# SCH_New_Project_2024-01-06.net
KiCad netlist of a schematic drawn in EasyEDA
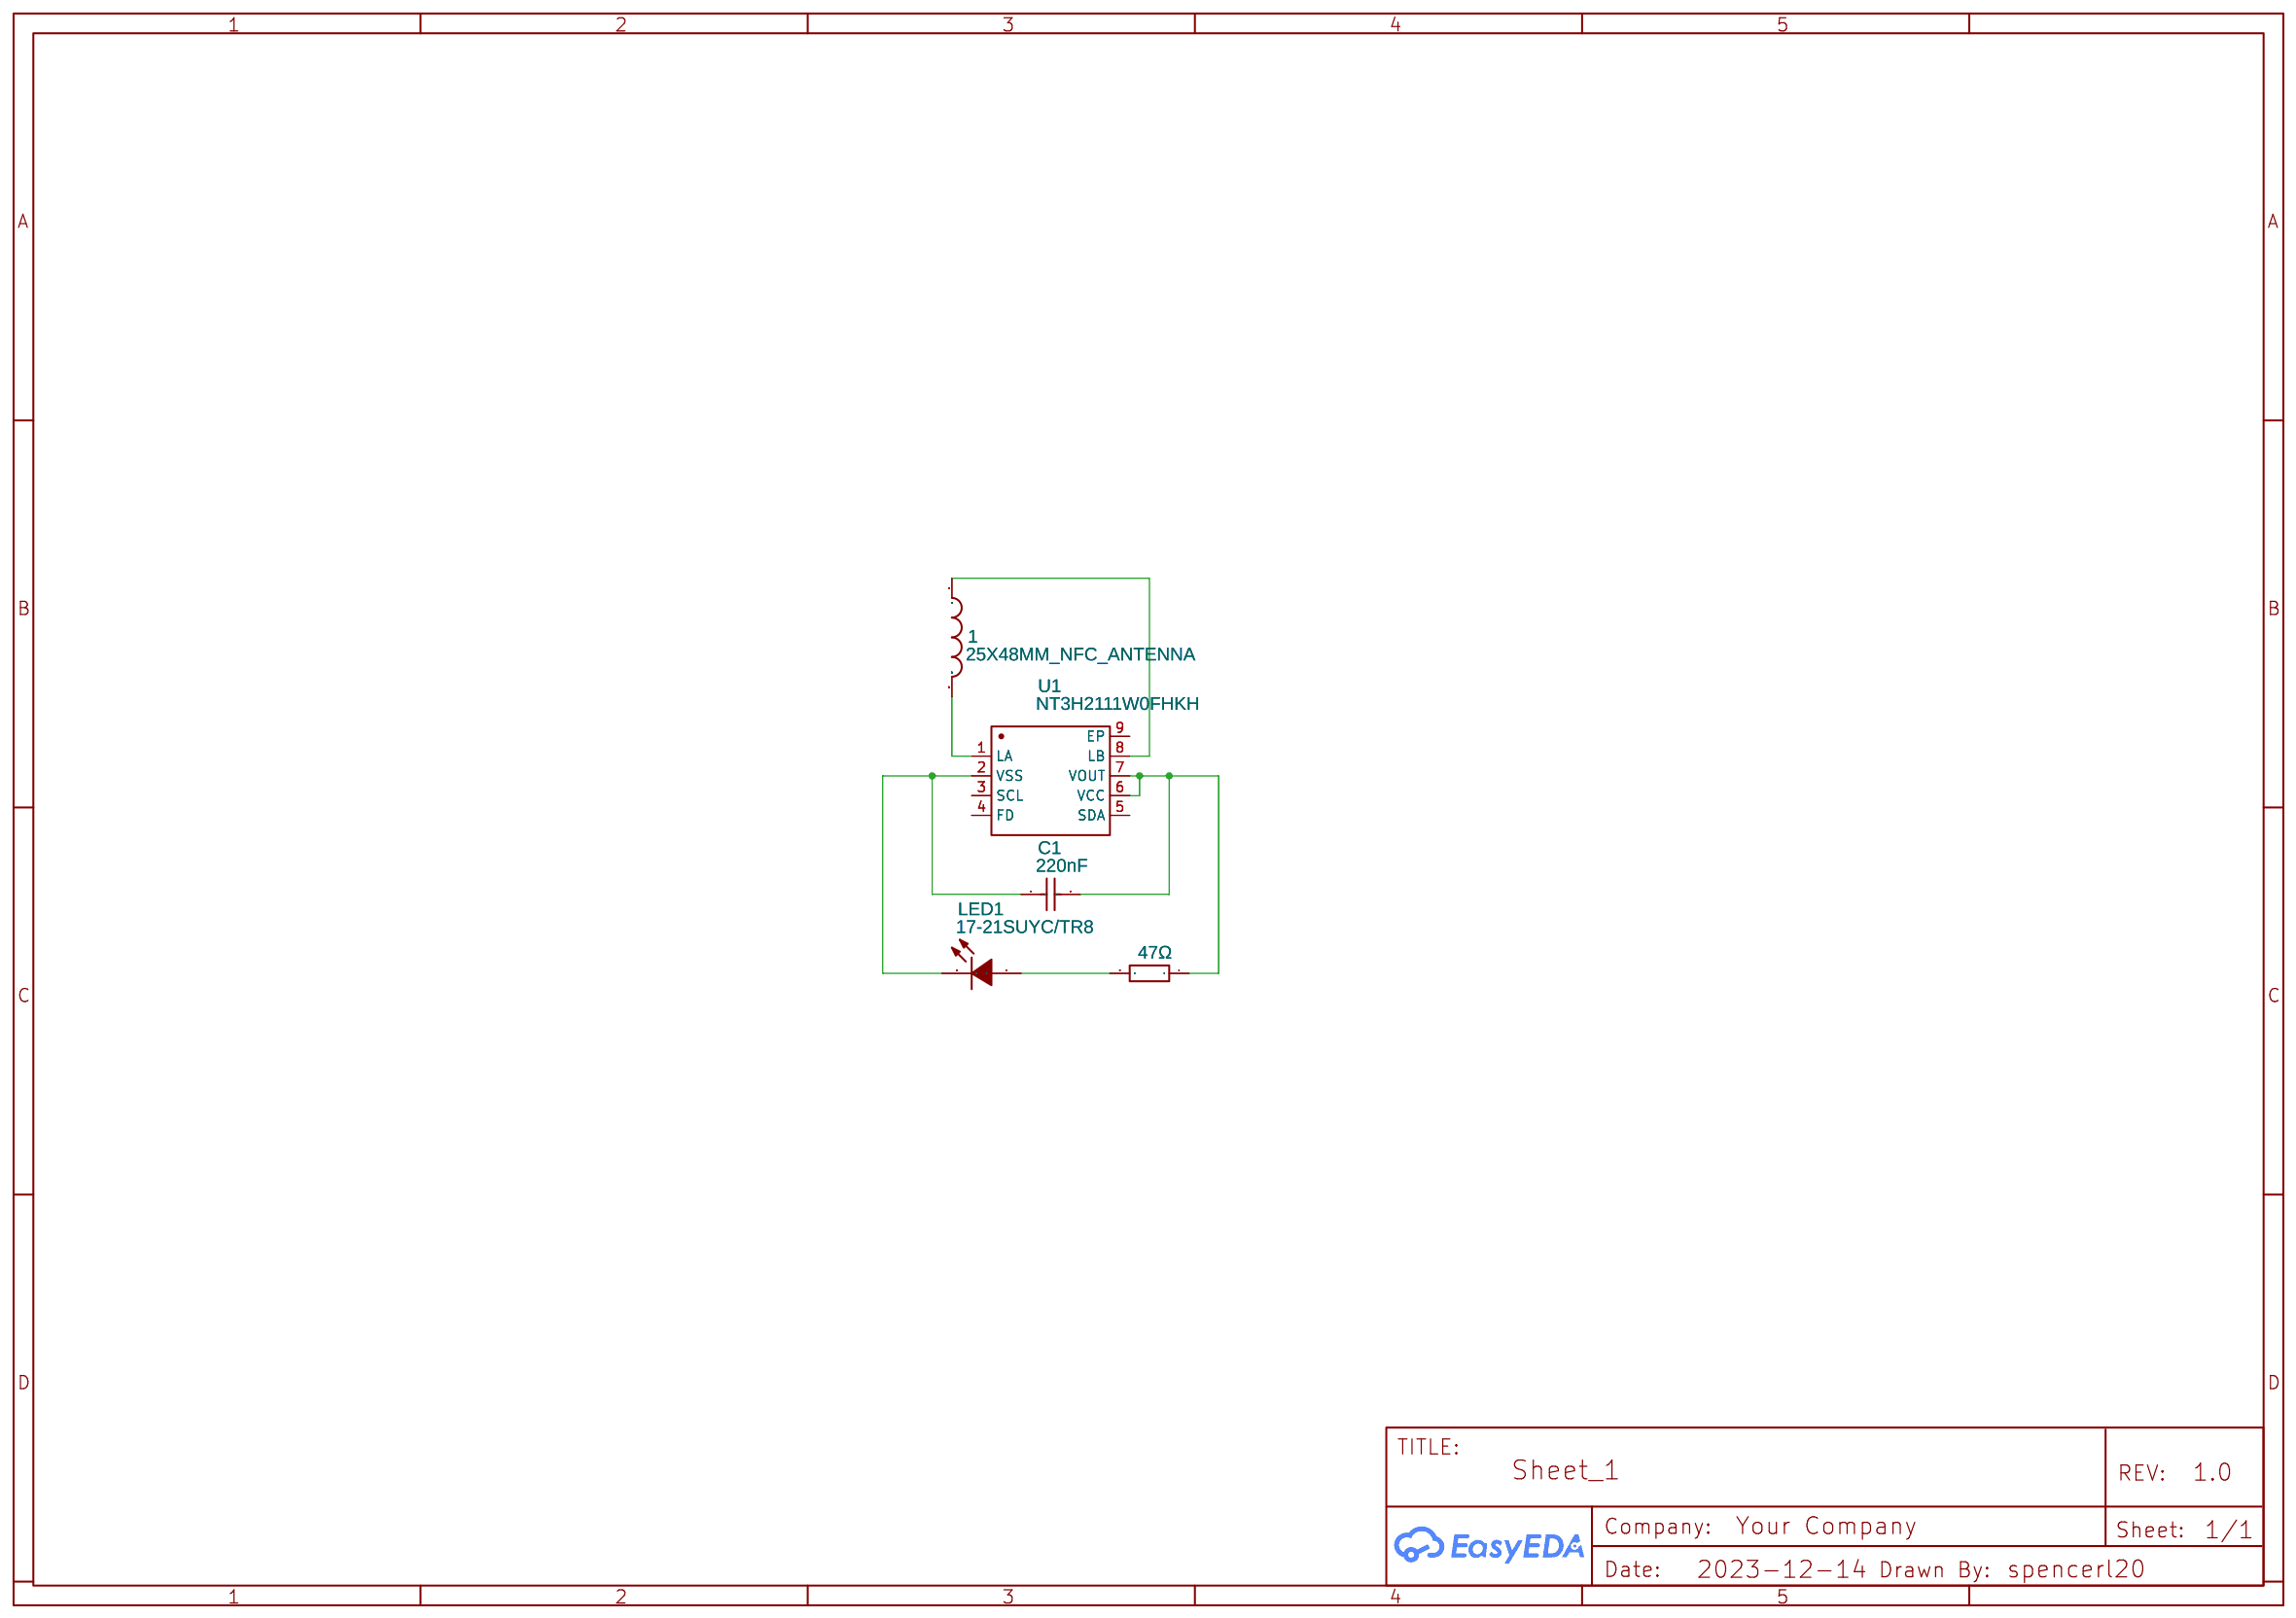
[diagram p0: schematic sheet]

(export (version "E")
  (design (tool "Eeschema 10.0.6"))
  (components
    (comp (ref "1") (value "25X48MM_NFC_ANTENNA") (libsource (lib "") (part "25X48MM_NFC_ANTENNA")))
    (comp (ref "C1")
      (value "220nF")
      (fields
        (field (name "Manufacturer Part") "CL10B224KA8NNNC")
        (field (name "Manufacturer") "SAMSUNG(三星)")
      )
      (libsource (lib "") (part "CL10B224KA8NNNC"))
    )
    (comp (ref "LED1")
      (value "17-21SUYC/TR8")
      (fields (field (name "Manufacturer Part") "KT-0805黄灯") (field (name "Manufacturer") "KENTO"))
      (libsource (lib "") (part "17-21SUYC/TR8"))
    )
    (comp (ref "R1")
      (value "47Ω")
      (fields
        (field (name "Manufacturer Part") "0603WAF470JT5E")
        (field (name "Manufacturer") "UNI-ROYAL(厚声)")
      )
      (libsource (lib "") (part "0603WAF470JT5E"))
    )
    (comp (ref "U1")
      (value "NT3H2111W0FHKH")
      (fields (field (name "Manufacturer") "NXP(恩智浦)"))
      (libsource (lib "") (part "NT3H2111W0FHKH"))
    )
  )
  (nets
    (net (code "1") (name "Net-(LED1-+)") (class "Default")
      (node (ref "LED1") (pin "1") (pinfunction "+_1") (pintype "unspecified"))
      (node (ref "R1") (pin "2") (pinfunction "2_2") (pintype "input"))
    )
    (net (code "2") (name "Net-(LED1--)") (class "Default")
      (node (ref "C1") (pin "1") (pinfunction "1_1") (pintype "input"))
      (node (ref "LED1") (pin "2") (pinfunction "-_2") (pintype "unspecified"))
      (node (ref "U1") (pin "2") (pinfunction "VSS_2") (pintype "unspecified"))
    )
    (net (code "3") (name "Net-(U1-LA)") (class "Default")
      (node (ref "1") (pin "P$2") (pinfunction "P$2_P$2") (pintype "bidirectional"))
      (node (ref "U1") (pin "1") (pinfunction "LA_1") (pintype "unspecified"))
    )
    (net (code "4") (name "Net-(U1-LB)") (class "Default")
      (node (ref "1") (pin "P$1") (pinfunction "P$1_P$1") (pintype "bidirectional"))
      (node (ref "U1") (pin "8") (pinfunction "LB_8") (pintype "unspecified"))
    )
    (net (code "5") (name "Net-(U1-VCC)") (class "Default")
      (node (ref "C1") (pin "2") (pinfunction "2_2") (pintype "input"))
      (node (ref "R1") (pin "1") (pinfunction "1_1") (pintype "input"))
      (node (ref "U1") (pin "6") (pinfunction "VCC_6") (pintype "unspecified"))
      (node (ref "U1") (pin "7") (pinfunction "VOUT_7") (pintype "unspecified"))
    )
    (net (code "6") (name "unconnected-(U1-EP-Pad9)") (class "Default")
      (node (ref "U1") (pin "9") (pinfunction "EP_9") (pintype "unspecified"))
    )
    (net (code "7") (name "unconnected-(U1-FD-Pad4)") (class "Default")
      (node (ref "U1") (pin "4") (pinfunction "FD_4") (pintype "unspecified"))
    )
    (net (code "8") (name "unconnected-(U1-SCL-Pad3)") (class "Default")
      (node (ref "U1") (pin "3") (pinfunction "SCL_3") (pintype "unspecified"))
    )
    (net (code "9") (name "unconnected-(U1-SDA-Pad5)") (class "Default")
      (node (ref "U1") (pin "5") (pinfunction "SDA_5") (pintype "unspecified"))
    )
  )
)
